# MP3.net
KiCad netlist of a schematic drawn in Altium Designer
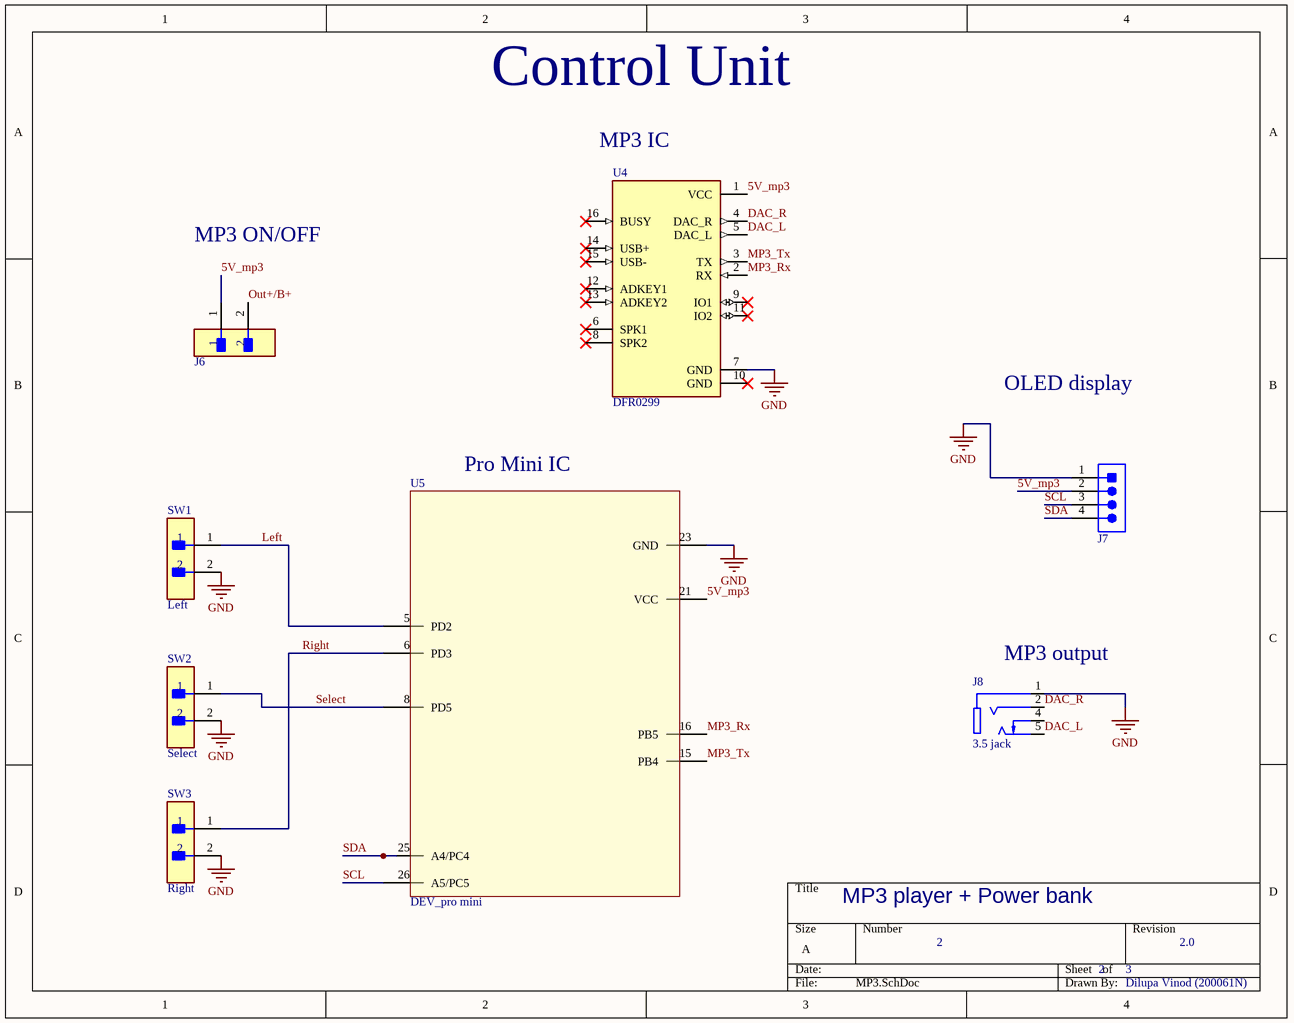
[diagram p0: MP3.SchDoc]

(export (version "E")
  (design (tool "Eeschema 10.0.6"))
  (components
    (comp (ref "J6")
      (value "SW_Mp3_p")
      (footprint "FP-M22-2510205-MFG")
      (description "CONN HEADER VERT 2POS 2MM")
      (fields
        (field (name "MANUFACTURER") "Harwin")
        (field (name "OCTOPART") "https://octopart.com/m22-2510205-harwin-2538221")
      )
      (libsource (lib "Altium Content Vault") (part "3bc925449376181038e59eaffc5286c"))
    )
    (comp (ref "J7")
      (value "OLED1")
      (footprint "TECO-640456-4")
      (description "Male Header, Pitch 2.54 mm, 1 x 4 Position, Height 10.03 mm, Tail Length 3.56 mm, RoHS, Bulk")
      (fields
        (field (name "MANUFACTURER") "TE Connectivity")
        (field (name "MANUFACTURER PART NUMBER") "640456-4")
      )
      (libsource (lib "MP3") (part "CMP-2000-05419-1"))
    )
    (comp (ref "J8")
      (value "3.5 jack")
      (footprint "SWITCHCRAFT_35RAPC3BH3")
      (fields (field (name "MP") "35RAPC3BH3"))
      (libsource (lib "MP3") (part "35RAPC3BH3"))
    )
    (comp (ref "SW1")
      (value "Left")
      (footprint "FP-M22-2510205-MFG")
      (description "CONN HEADER VERT 2POS 2MM")
      (fields
        (field (name "MANUFACTURER") "Harwin")
        (field (name "OCTOPART") "https://octopart.com/m22-2510205-harwin-2538221")
      )
      (libsource (lib "") (part "3bc925449376181038e59eaffc5286c_1"))
    )
    (comp (ref "SW2")
      (value "Select")
      (footprint "FP-M22-2510205-MFG")
      (description "CONN HEADER VERT 2POS 2MM")
      (fields
        (field (name "MANUFACTURER") "Harwin")
        (field (name "OCTOPART") "https://octopart.com/m22-2510205-harwin-2538221")
      )
      (libsource (lib "") (part "3bc925449376181038e59eaffc5286c_1"))
    )
    (comp (ref "SW3")
      (value "Right")
      (footprint "FP-M22-2510205-MFG")
      (description "CONN HEADER VERT 2POS 2MM")
      (fields
        (field (name "MANUFACTURER") "Harwin")
        (field (name "OCTOPART") "https://octopart.com/m22-2510205-harwin-2538221")
      )
      (libsource (lib "") (part "3bc925449376181038e59eaffc5286c_1"))
    )
    (comp (ref "U4")
      (value "DFR0299")
      (footprint "MODULE_DFR0299")
      (description "Dfplayer - a Mini Mp3 Player")
      (libsource (lib "MP3") (part "DFR0299"))
    )
    (comp (ref "U5")
      (value "DEV_pro mini")
      (footprint "PCBComponent_1 - duplicate")
      (libsource (lib "Final") (part "DEV_pro mini"))
    )
  )
  (nets
    (net (code "1") (name "/5V_mp3") (class "Default")
      (node (ref "J6") (pin "1") (pinfunction "1_1") (pintype "passive"))
      (node (ref "J7") (pin "2") (pinfunction "2_2") (pintype "passive"))
      (node (ref "U4") (pin "1") (pinfunction "VCC_1") (pintype "power_in"))
      (node (ref "U5") (pin "21") (pinfunction "VCC_21") (pintype "passive"))
    )
    (net (code "2") (name "/DAC_L") (class "Default")
      (node (ref "J8") (pin "5") (pinfunction "5_5") (pintype "passive"))
      (node (ref "U4") (pin "5") (pinfunction "DAC_L_5") (pintype "output"))
    )
    (net (code "3") (name "/DAC_R") (class "Default")
      (node (ref "J8") (pin "2") (pinfunction "2_2") (pintype "passive"))
      (node (ref "U4") (pin "4") (pinfunction "DAC_R_4") (pintype "output"))
    )
    (net (code "4") (name "/Left") (class "Default")
      (node (ref "SW1") (pin "1") (pinfunction "1_1") (pintype "passive"))
      (node (ref "U5") (pin "5") (pinfunction "PD2_5") (pintype "passive"))
    )
    (net (code "5") (name "/MP3_Rx") (class "Default")
      (node (ref "U4") (pin "2") (pinfunction "RX_2") (pintype "input"))
      (node (ref "U5") (pin "16") (pinfunction "PB5_16") (pintype "passive"))
    )
    (net (code "6") (name "/MP3_Tx") (class "Default")
      (node (ref "U4") (pin "3") (pinfunction "TX_3") (pintype "output"))
      (node (ref "U5") (pin "15") (pinfunction "PB4_15") (pintype "passive"))
    )
    (net (code "7") (name "/Out+{slash}B+") (class "Default")
      (node (ref "J6") (pin "2") (pinfunction "2_2") (pintype "passive"))
    )
    (net (code "8") (name "/Right") (class "Default")
      (node (ref "SW3") (pin "1") (pinfunction "1_1") (pintype "passive"))
      (node (ref "U5") (pin "6") (pinfunction "PD3_6") (pintype "passive"))
    )
    (net (code "9") (name "/SCL") (class "Default")
      (node (ref "J7") (pin "3") (pinfunction "3_3") (pintype "passive"))
      (node (ref "U5") (pin "26") (pinfunction "A5/PC5_26") (pintype "passive"))
    )
    (net (code "10") (name "/SDA") (class "Default")
      (node (ref "J7") (pin "4") (pinfunction "4_4") (pintype "passive"))
      (node (ref "U5") (pin "25") (pinfunction "A4/PC4_25") (pintype "passive"))
    )
    (net (code "11") (name "/Select") (class "Default")
      (node (ref "SW2") (pin "1") (pinfunction "1_1") (pintype "passive"))
      (node (ref "U5") (pin "8") (pinfunction "PD5_8") (pintype "passive"))
    )
    (net (code "12") (name "GND") (class "Default")
      (node (ref "J7") (pin "1") (pinfunction "1_1") (pintype "passive"))
      (node (ref "J8") (pin "1") (pinfunction "1_1") (pintype "passive"))
      (node (ref "SW1") (pin "2") (pinfunction "2_2") (pintype "passive"))
      (node (ref "SW2") (pin "2") (pinfunction "2_2") (pintype "passive"))
      (node (ref "SW3") (pin "2") (pinfunction "2_2") (pintype "passive"))
      (node (ref "U4") (pin "7") (pinfunction "GND_7") (pintype "power_in"))
      (node (ref "U5") (pin "23") (pinfunction "GND_23") (pintype "passive"))
    )
    (net (code "13") (name "unconnected-(J8-Pad4)") (class "Default")
      (node (ref "J8") (pin "4") (pinfunction "4_4") (pintype "passive"))
    )
    (net (code "14") (name "unconnected-(U4-ADKEY1-Pad12)") (class "Default")
      (node (ref "U4") (pin "12") (pinfunction "ADKEY1_12") (pintype "input+no_connect"))
    )
    (net (code "15") (name "unconnected-(U4-ADKEY2-Pad13)") (class "Default")
      (node (ref "U4") (pin "13") (pinfunction "ADKEY2_13") (pintype "input+no_connect"))
    )
    (net (code "16") (name "unconnected-(U4-BUSY-Pad16)") (class "Default")
      (node (ref "U4") (pin "16") (pinfunction "BUSY_16") (pintype "input+no_connect"))
    )
    (net (code "17") (name "unconnected-(U4-GND-Pad10)") (class "Default")
      (node (ref "U4") (pin "10") (pinfunction "GND_10") (pintype "power_in+no_connect"))
    )
    (net (code "18") (name "unconnected-(U4-IO1-Pad9)") (class "Default")
      (node (ref "U4") (pin "9") (pinfunction "IO1_9") (pintype "bidirectional+no_connect"))
    )
    (net (code "19") (name "unconnected-(U4-IO2-Pad11)") (class "Default")
      (node (ref "U4") (pin "11") (pinfunction "IO2_11") (pintype "bidirectional+no_connect"))
    )
    (net (code "20") (name "unconnected-(U4-SPK1-Pad6)") (class "Default")
      (node (ref "U4") (pin "6") (pinfunction "SPK1_6") (pintype "passive+no_connect"))
    )
    (net (code "21") (name "unconnected-(U4-SPK2-Pad8)") (class "Default")
      (node (ref "U4") (pin "8") (pinfunction "SPK2_8") (pintype "passive+no_connect"))
    )
    (net (code "22") (name "unconnected-(U4-USB+-Pad14)") (class "Default")
      (node (ref "U4") (pin "14") (pinfunction "USB+_14") (pintype "input+no_connect"))
    )
    (net (code "23") (name "unconnected-(U4-USB--Pad15)") (class "Default")
      (node (ref "U4") (pin "15") (pinfunction "USB-_15") (pintype "input+no_connect"))
    )
  )
)
